# schematic.net
KiCad netlist of a schematic drawn in EasyEDA
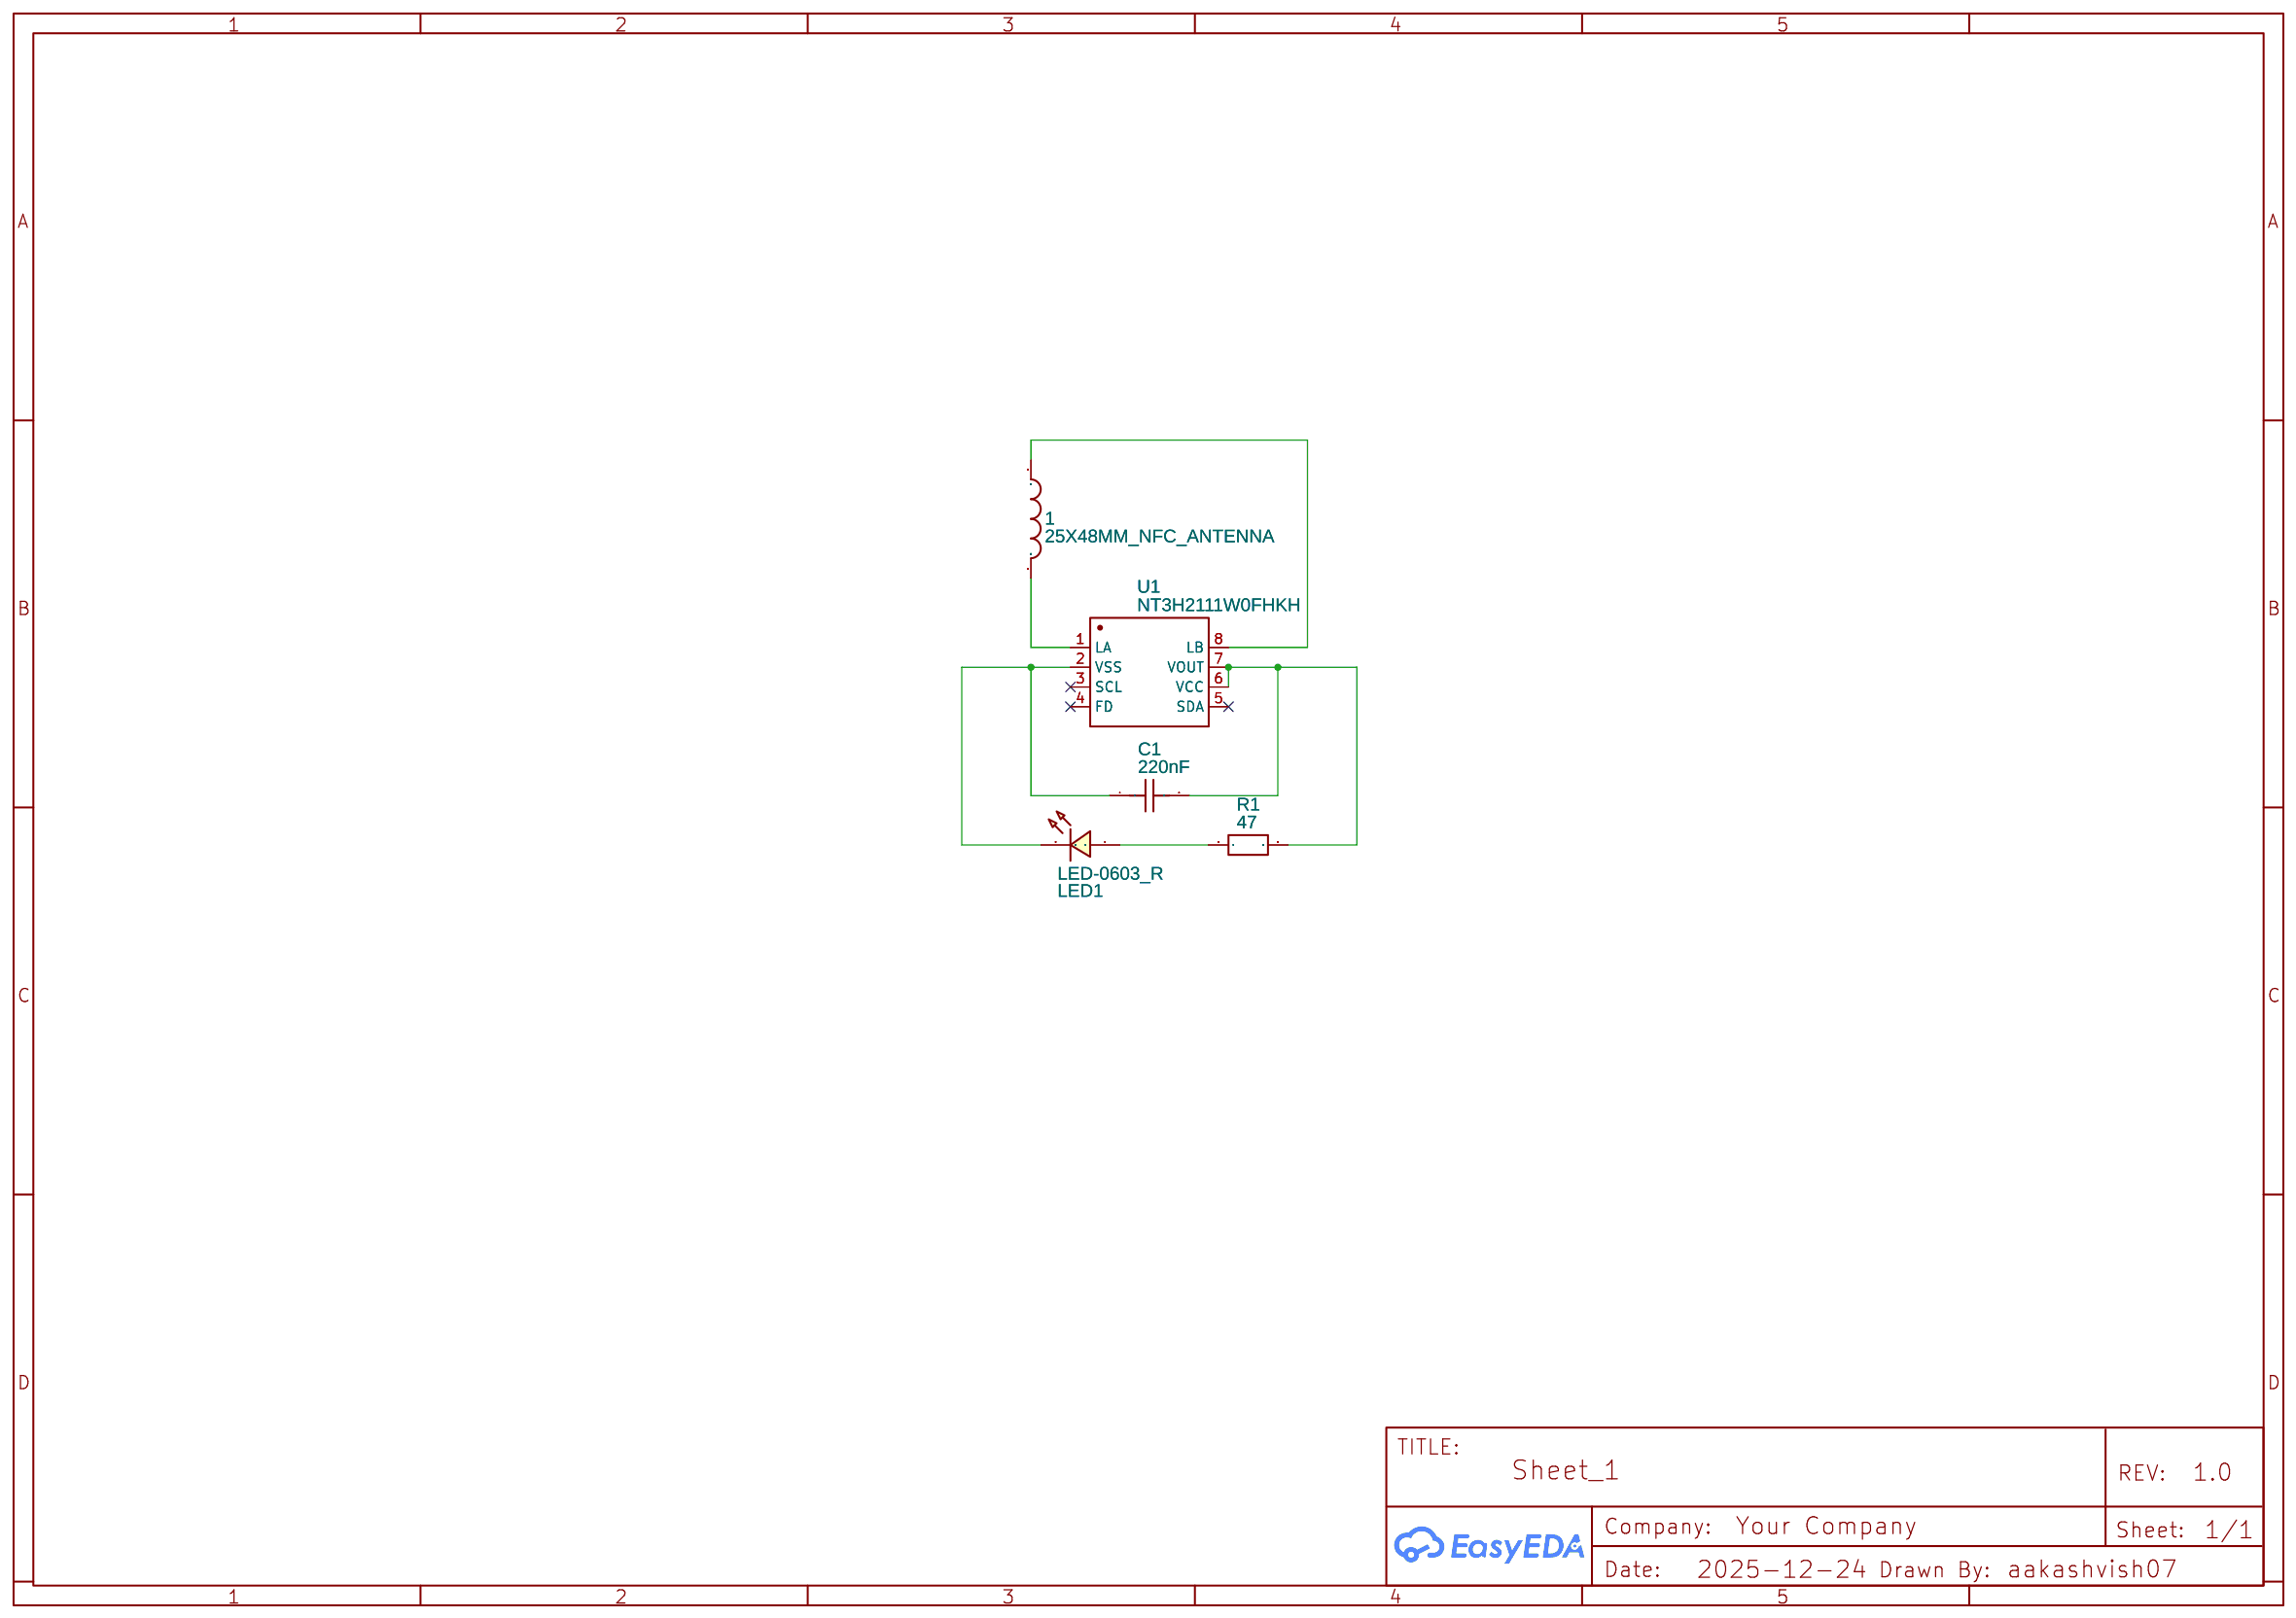
[diagram p0: schematic sheet]

(export (version "E")
  (design (tool "Eeschema 10.0.6"))
  (components
    (comp (ref "1") (value "25X48MM_NFC_ANTENNA") (libsource (lib "") (part "25X48MM_NFC_ANTENNA")))
    (comp (ref "C1") (value "220nF") (libsource (lib "") (part "C_0603_US")))
    (comp (ref "LED1")
      (value "LED-0603_R")
      (fields
        (field (name "Manufacturer Part") "19-217/R6C-AL1M2VY/3T")
        (field (name "Manufacturer") "EVERLIGHT(台湾亿光)")
      )
      (libsource (lib "") (part "LED-0603_R"))
    )
    (comp (ref "R1") (value "47") (libsource (lib "") (part "R_0603_EU")))
    (comp (ref "U1")
      (value "NT3H2111W0FHKH")
      (fields (field (name "Manufacturer") "NXP(恩智浦)"))
      (libsource (lib "") (part "NT3H2111W0FHKH"))
    )
  )
  (nets
    (net (code "1") (name "Net-(LED1-Pad1)") (class "Default")
      (node (ref "LED1") (pin "1") (pinfunction "1_1") (pintype "unspecified"))
      (node (ref "R1") (pin "1") (pinfunction "1_1") (pintype "unspecified"))
    )
    (net (code "2") (name "Net-(U1-LA)") (class "Default")
      (node (ref "1") (pin "P$2") (pinfunction "P$2_P$2") (pintype "bidirectional"))
      (node (ref "U1") (pin "1") (pinfunction "LA_1") (pintype "unspecified"))
    )
    (net (code "3") (name "Net-(U1-LB)") (class "Default")
      (node (ref "1") (pin "P$1") (pinfunction "P$1_P$1") (pintype "bidirectional"))
      (node (ref "U1") (pin "8") (pinfunction "LB_8") (pintype "unspecified"))
    )
    (net (code "4") (name "Net-(U1-VCC)") (class "Default")
      (node (ref "C1") (pin "2") (pinfunction "2_2") (pintype "unspecified"))
      (node (ref "R1") (pin "2") (pinfunction "2_2") (pintype "unspecified"))
      (node (ref "U1") (pin "6") (pinfunction "VCC_6") (pintype "unspecified"))
      (node (ref "U1") (pin "7") (pinfunction "VOUT_7") (pintype "unspecified"))
    )
    (net (code "5") (name "Net-(U1-VSS)") (class "Default")
      (node (ref "C1") (pin "1") (pinfunction "1_1") (pintype "unspecified"))
      (node (ref "LED1") (pin "2") (pinfunction "2_2") (pintype "unspecified"))
      (node (ref "U1") (pin "2") (pinfunction "VSS_2") (pintype "unspecified"))
    )
    (net (code "6") (name "unconnected-(U1-FD-Pad4)") (class "Default")
      (node (ref "U1") (pin "4") (pinfunction "FD_4") (pintype "unspecified+no_connect"))
    )
    (net (code "7") (name "unconnected-(U1-SCL-Pad3)") (class "Default")
      (node (ref "U1") (pin "3") (pinfunction "SCL_3") (pintype "unspecified+no_connect"))
    )
    (net (code "8") (name "unconnected-(U1-SDA-Pad5)") (class "Default")
      (node (ref "U1") (pin "5") (pinfunction "SDA_5") (pintype "unspecified+no_connect"))
    )
  )
)
